# ZigBee.net
KiCad netlist of a schematic drawn in Altium Designer
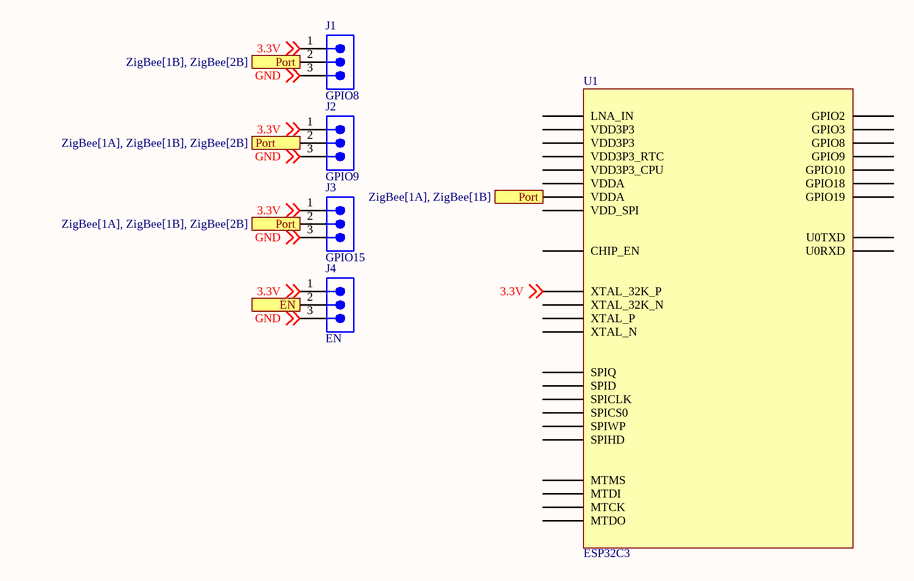
[diagram p0: ZigBee.SchDoc]

(export (version "E")
  (design (tool "Eeschema 10.0.6"))
  (components
    (comp (ref "J1")
      (value "GPIO8")
      (footprint "61300311121")
      (libsource (lib "Altium Content Vault") (part "Header_Male_1R_03P"))
    )
    (comp (ref "J2")
      (value "GPIO9")
      (footprint "61300311121")
      (libsource (lib "Altium Content Vault") (part "Header_Male_1R_03P"))
    )
    (comp (ref "J3")
      (value "GPIO15")
      (footprint "61300311121")
      (libsource (lib "Altium Content Vault") (part "Header_Male_1R_03P"))
    )
    (comp (ref "J4")
      (value "EN")
      (footprint "61300311121")
      (libsource (lib "Altium Content Vault") (part "Header_Male_1R_03P"))
    )
    (comp (ref "U1")
      (value "ESP32C3")
      (footprint "QFN50P500X500X90_HS-33N")
      (libsource (lib "Schlib1") (part "ESP32C3"))
    )
  )
  (nets
    (net (code "1") (name "/EN") (class "Default")
      (node (ref "J4") (pin "2") (pinfunction "2_2") (pintype "passive"))
    )
    (net (code "2") (name "/Port") (class "Default")
      (node (ref "J1") (pin "2") (pinfunction "2_2") (pintype "passive"))
      (node (ref "J2") (pin "2") (pinfunction "2_2") (pintype "passive"))
      (node (ref "J3") (pin "2") (pinfunction "2_2") (pintype "passive"))
      (node (ref "U1") (pin "31") (pinfunction "VDDA_31") (pintype "passive"))
    )
    (net (code "3") (name "3.3V") (class "Default")
      (node (ref "J1") (pin "1") (pinfunction "1_1") (pintype "passive"))
      (node (ref "J2") (pin "1") (pinfunction "1_1") (pintype "passive"))
      (node (ref "J3") (pin "1") (pinfunction "1_1") (pintype "passive"))
      (node (ref "J4") (pin "1") (pinfunction "1_1") (pintype "passive"))
      (node (ref "U1") (pin "4") (pinfunction "XTAL_32K_P_4") (pintype "passive"))
    )
    (net (code "4") (name "GND") (class "Default")
      (node (ref "J1") (pin "3") (pinfunction "3_3") (pintype "passive"))
      (node (ref "J2") (pin "3") (pinfunction "3_3") (pintype "passive"))
      (node (ref "J3") (pin "3") (pinfunction "3_3") (pintype "passive"))
      (node (ref "J4") (pin "3") (pinfunction "3_3") (pintype "passive"))
    )
    (net (code "5") (name "unconnected-(U1-CHIP_EN-Pad7)") (class "Default")
      (node (ref "U1") (pin "7") (pinfunction "CHIP_EN_7") (pintype "passive"))
    )
    (net (code "6") (name "unconnected-(U1-GPIO2-Pad6)") (class "Default")
      (node (ref "U1") (pin "6") (pinfunction "GPIO2_6") (pintype "passive"))
    )
    (net (code "7") (name "unconnected-(U1-GPIO3-Pad8)") (class "Default")
      (node (ref "U1") (pin "8") (pinfunction "GPIO3_8") (pintype "passive"))
    )
    (net (code "8") (name "unconnected-(U1-GPIO8-Pad14)") (class "Default")
      (node (ref "U1") (pin "14") (pinfunction "GPIO8_14") (pintype "passive"))
    )
    (net (code "9") (name "unconnected-(U1-GPIO9-Pad15)") (class "Default")
      (node (ref "U1") (pin "15") (pinfunction "GPIO9_15") (pintype "passive"))
    )
    (net (code "10") (name "unconnected-(U1-GPIO10-Pad16)") (class "Default")
      (node (ref "U1") (pin "16") (pinfunction "GPIO10_16") (pintype "passive"))
    )
    (net (code "11") (name "unconnected-(U1-GPIO18-Pad25)") (class "Default")
      (node (ref "U1") (pin "25") (pinfunction "GPIO18_25") (pintype "passive"))
    )
    (net (code "12") (name "unconnected-(U1-GPIO19-Pad26)") (class "Default")
      (node (ref "U1") (pin "26") (pinfunction "GPIO19_26") (pintype "passive"))
    )
    (net (code "13") (name "unconnected-(U1-LNA_IN-Pad1)") (class "Default")
      (node (ref "U1") (pin "1") (pinfunction "LNA_IN_1") (pintype "passive"))
    )
    (net (code "14") (name "unconnected-(U1-MTCK-Pad12)") (class "Default")
      (node (ref "U1") (pin "12") (pinfunction "MTCK_12") (pintype "passive"))
    )
    (net (code "15") (name "unconnected-(U1-MTDI-Pad10)") (class "Default")
      (node (ref "U1") (pin "10") (pinfunction "MTDI_10") (pintype "passive"))
    )
    (net (code "16") (name "unconnected-(U1-MTDO-Pad13)") (class "Default")
      (node (ref "U1") (pin "13") (pinfunction "MTDO_13") (pintype "passive"))
    )
    (net (code "17") (name "unconnected-(U1-MTMS-Pad9)") (class "Default")
      (node (ref "U1") (pin "9") (pinfunction "MTMS_9") (pintype "passive"))
    )
    (net (code "18") (name "unconnected-(U1-SPICLK-Pad22)") (class "Default")
      (node (ref "U1") (pin "22") (pinfunction "SPICLK_22") (pintype "passive"))
    )
    (net (code "19") (name "unconnected-(U1-SPICS0-Pad21)") (class "Default")
      (node (ref "U1") (pin "21") (pinfunction "SPICS0_21") (pintype "passive"))
    )
    (net (code "20") (name "unconnected-(U1-SPID-Pad23)") (class "Default")
      (node (ref "U1") (pin "23") (pinfunction "SPID_23") (pintype "passive"))
    )
    (net (code "21") (name "unconnected-(U1-SPIHD-Pad19)") (class "Default")
      (node (ref "U1") (pin "19") (pinfunction "SPIHD_19") (pintype "passive"))
    )
    (net (code "22") (name "unconnected-(U1-SPIQ-Pad24)") (class "Default")
      (node (ref "U1") (pin "24") (pinfunction "SPIQ_24") (pintype "passive"))
    )
    (net (code "23") (name "unconnected-(U1-SPIWP-Pad20)") (class "Default")
      (node (ref "U1") (pin "20") (pinfunction "SPIWP_20") (pintype "passive"))
    )
    (net (code "24") (name "unconnected-(U1-U0RXD-Pad27)") (class "Default")
      (node (ref "U1") (pin "27") (pinfunction "U0RXD_27") (pintype "passive"))
    )
    (net (code "25") (name "unconnected-(U1-U0TXD-Pad28)") (class "Default")
      (node (ref "U1") (pin "28") (pinfunction "U0TXD_28") (pintype "passive"))
    )
    (net (code "26") (name "unconnected-(U1-VDD3P3-Pad2)") (class "Default")
      (node (ref "U1") (pin "2") (pinfunction "VDD3P3_2") (pintype "passive"))
    )
    (net (code "27") (name "unconnected-(U1-VDD3P3-Pad3)") (class "Default")
      (node (ref "U1") (pin "3") (pinfunction "VDD3P3_3") (pintype "passive"))
    )
    (net (code "28") (name "unconnected-(U1-VDD3P3_CPU-Pad17)") (class "Default")
      (node (ref "U1") (pin "17") (pinfunction "VDD3P3_CPU_17") (pintype "passive"))
    )
    (net (code "29") (name "unconnected-(U1-VDD3P3_RTC-Pad11)") (class "Default")
      (node (ref "U1") (pin "11") (pinfunction "VDD3P3_RTC_11") (pintype "passive"))
    )
    (net (code "30") (name "unconnected-(U1-VDDA-Pad32)") (class "Default")
      (node (ref "U1") (pin "32") (pinfunction "VDDA_32") (pintype "passive"))
    )
    (net (code "31") (name "unconnected-(U1-VDD_SPI-Pad18)") (class "Default")
      (node (ref "U1") (pin "18") (pinfunction "VDD_SPI_18") (pintype "passive"))
    )
    (net (code "32") (name "unconnected-(U1-XTAL_32K_N-Pad5)") (class "Default")
      (node (ref "U1") (pin "5") (pinfunction "XTAL_32K_N_5") (pintype "passive"))
    )
    (net (code "33") (name "unconnected-(U1-XTAL_N-Pad29)") (class "Default")
      (node (ref "U1") (pin "29") (pinfunction "XTAL_N_29") (pintype "passive"))
    )
    (net (code "34") (name "unconnected-(U1-XTAL_P-Pad30)") (class "Default")
      (node (ref "U1") (pin "30") (pinfunction "XTAL_P_30") (pintype "passive"))
    )
  )
)
